# Sheet1.net
KiCad netlist of a schematic drawn in Altium Designer
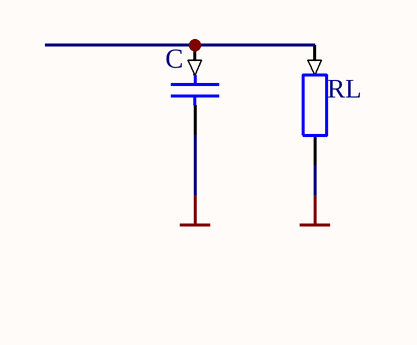
[diagram p0: Sheet1.SchDoc]

(export (version "E")
  (design (tool "Eeschema 10.0.6"))
  (components
    (comp (ref "C")
      (value "Cap")
      (footprint "RAD-0.3")
      (description "Capacitor")
      (fields (field (name "PUBLISHER") "Altium Limited"))
      (libsource (lib "Miscellaneous Devices") (part "Cap"))
    )
    (comp (ref "RL")
      (value "Res2")
      (footprint "AXIAL-0.4")
      (description "Resistor")
      (fields (field (name "PUBLISHER") "Altium Limited"))
      (libsource (lib "Miscellaneous Devices") (part "Res2"))
    )
  )
  (nets
    (net (code "1") (name "GND") (class "Default")
      (node (ref "C") (pin "2") (pinfunction "2_2") (pintype "passive"))
      (node (ref "RL") (pin "1") (pinfunction "1_1") (pintype "passive"))
    )
    (net (code "2") (name "Net-(C-Pad1)") (class "Default")
      (node (ref "C") (pin "1") (pinfunction "1_1") (pintype "input"))
      (node (ref "RL") (pin "2") (pinfunction "2_2") (pintype "input"))
    )
  )
)
